# Dentist_camera_extender_schematic_sch_3.net
KiCad netlist of a schematic drawn in Altium Designer
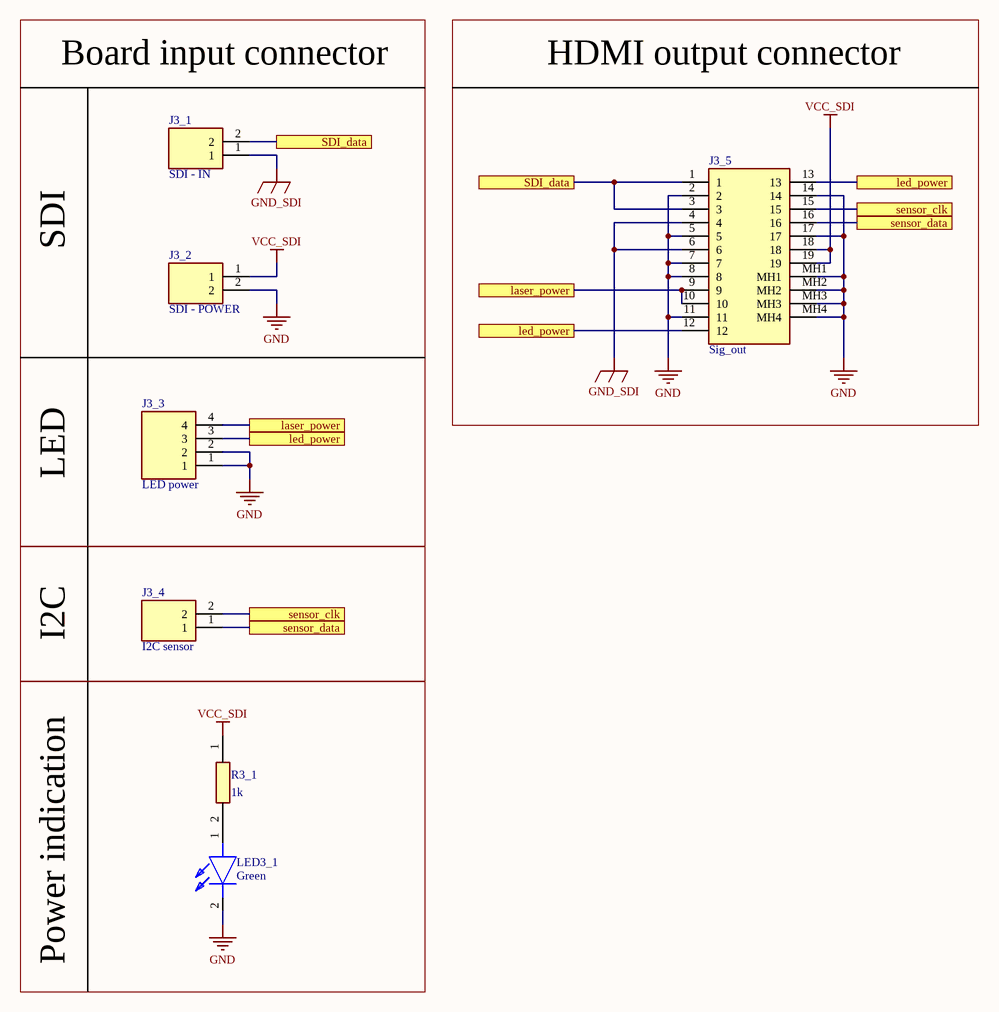
[diagram p0: Dentist_camera_extender_schematic_sch_3.SchDoc]

(export (version "E")
  (design (tool "Eeschema 10.0.6"))
  (components
    (comp (ref "J3_1")
      (value "SDI - IN")
      (footprint "SamacSys:B02BJWPFSKRLFSN")
      (description "Connector")
      (fields (field (name "MANUFACTURER_PART_NUMBER") "B02B-JWPF-SK-R(LF)(SN)"))
      (libsource (lib "") (part "B02B-JWPF-SK-R_LF__SN__1"))
    )
    (comp (ref "J3_2")
      (value "SDI - POWER")
      (footprint "SamacSys:B02BJWPFSKRLFSN")
      (description "Connector")
      (fields (field (name "MANUFACTURER_PART_NUMBER") "B02B-JWPF-SK-R(LF)(SN)"))
      (libsource (lib "SamacSys") (part "B02B-JWPF-SK-R_LF__SN_"))
    )
    (comp (ref "J3_3")
      (value "LED power")
      (footprint "SamacSys:B04BJWPFSKRLFSN")
      (description "Connector")
      (fields (field (name "MANUFACTURER_PART_NUMBER") "B04B-JWPF-SK-R(LF)(SN)"))
      (libsource (lib "SamacSys") (part "B04B-JWPF-SK-R_LF__SN_"))
    )
    (comp (ref "J3_4")
      (value "I2C sensor")
      (footprint "SamacSys:B02BJWPFSKRLFSN")
      (description "Connector")
      (fields (field (name "MANUFACTURER_PART_NUMBER") "B02B-JWPF-SK-R(LF)(SN)"))
      (libsource (lib "") (part "B02B-JWPF-SK-R_LF__SN__1"))
    )
    (comp (ref "J3_5")
      (value "Sig_out")
      (footprint "SamacSys:10029449001RLF")
      (description "10029449-001RLF")
      (fields (field (name "MOUSER PART NUMBER") "649-10029449-001RLF"))
      (libsource (lib "SamacSys") (part "10029449-001RLF"))
    )
    (comp (ref "LED3_1")
      (value "Green")
      (footprint "SamacSys:1721SYGCS530E2TR8")
      (description "LED")
      (fields
        (field (name "MANUFACTURER_PART_NUMBER") "17-21SYGC/S530-E2/TR8")
        (field (name "MOUSER PART NUMBER") "638-1721SYGCS530E2")
      )
      (libsource (lib "SamacSys") (part "17-21SYGC_S530-E2_TR8"))
    )
    (comp (ref "R3_1")
      (value "1k")
      (footprint "SamacSys:ERA6AEB1020V")
      (description "ERA6ARB103V")
      (libsource (lib "SamacSys") (part "ERA6ARB103V"))
    )
  )
  (nets
    (net (code "1") (name "/SDI_data") (class "Default")
      (node (ref "J3_1") (pin "2") (pinfunction "2_2") (pintype "passive"))
      (node (ref "J3_5") (pin "1") (pinfunction "1_1") (pintype "passive"))
      (node (ref "J3_5") (pin "3") (pinfunction "3_3") (pintype "passive"))
    )
    (net (code "2") (name "/laser_power") (class "Default")
      (node (ref "J3_3") (pin "4") (pinfunction "4_4") (pintype "passive"))
      (node (ref "J3_5") (pin "10") (pinfunction "10_10") (pintype "passive"))
      (node (ref "J3_5") (pin "9") (pinfunction "9_9") (pintype "passive"))
    )
    (net (code "3") (name "/led_power") (class "Default")
      (node (ref "J3_3") (pin "3") (pinfunction "3_3") (pintype "passive"))
      (node (ref "J3_5") (pin "12") (pinfunction "12_12") (pintype "passive"))
      (node (ref "J3_5") (pin "13") (pinfunction "13_13") (pintype "passive"))
    )
    (net (code "4") (name "/sensor_clk") (class "Default")
      (node (ref "J3_4") (pin "2") (pinfunction "2_2") (pintype "passive"))
      (node (ref "J3_5") (pin "15") (pinfunction "15_15") (pintype "passive"))
    )
    (net (code "5") (name "/sensor_data") (class "Default")
      (node (ref "J3_4") (pin "1") (pinfunction "1_1") (pintype "passive"))
      (node (ref "J3_5") (pin "16") (pinfunction "16_16") (pintype "passive"))
    )
    (net (code "6") (name "GND") (class "Default")
      (node (ref "J3_2") (pin "2") (pinfunction "2_2") (pintype "passive"))
      (node (ref "J3_3") (pin "1") (pinfunction "1_1") (pintype "passive"))
      (node (ref "J3_3") (pin "2") (pinfunction "2_2") (pintype "passive"))
      (node (ref "J3_5") (pin "11") (pinfunction "11_11") (pintype "passive"))
      (node (ref "J3_5") (pin "14") (pinfunction "14_14") (pintype "passive"))
      (node (ref "J3_5") (pin "17") (pinfunction "17_17") (pintype "passive"))
      (node (ref "J3_5") (pin "2") (pinfunction "2_2") (pintype "passive"))
      (node (ref "J3_5") (pin "5") (pinfunction "5_5") (pintype "passive"))
      (node (ref "J3_5") (pin "7") (pinfunction "7_7") (pintype "passive"))
      (node (ref "J3_5") (pin "8") (pinfunction "8_8") (pintype "passive"))
      (node (ref "J3_5") (pin "MH1") (pinfunction "MH1_MH1") (pintype "passive"))
      (node (ref "J3_5") (pin "MH2") (pinfunction "MH2_MH2") (pintype "passive"))
      (node (ref "J3_5") (pin "MH3") (pinfunction "MH3_MH3") (pintype "passive"))
      (node (ref "J3_5") (pin "MH4") (pinfunction "MH4_MH4") (pintype "passive"))
      (node (ref "LED3_1") (pin "2") (pinfunction "K_2") (pintype "passive"))
    )
    (net (code "7") (name "GND_SDI") (class "Default")
      (node (ref "J3_1") (pin "1") (pinfunction "1_1") (pintype "passive"))
      (node (ref "J3_5") (pin "4") (pinfunction "4_4") (pintype "passive"))
      (node (ref "J3_5") (pin "6") (pinfunction "6_6") (pintype "passive"))
    )
    (net (code "8") (name "Net-(LED3_1-A)") (class "Default")
      (node (ref "LED3_1") (pin "1") (pinfunction "A_1") (pintype "passive"))
      (node (ref "R3_1") (pin "2") (pinfunction "2_2") (pintype "passive"))
    )
    (net (code "9") (name "VCC_SDI") (class "Default")
      (node (ref "J3_2") (pin "1") (pinfunction "1_1") (pintype "passive"))
      (node (ref "J3_5") (pin "18") (pinfunction "18_18") (pintype "passive"))
      (node (ref "J3_5") (pin "19") (pinfunction "19_19") (pintype "passive"))
      (node (ref "R3_1") (pin "1") (pinfunction "1_1") (pintype "passive"))
    )
  )
)
